# DAC_12bit.net
KiCad netlist of a schematic drawn in Altium Designer
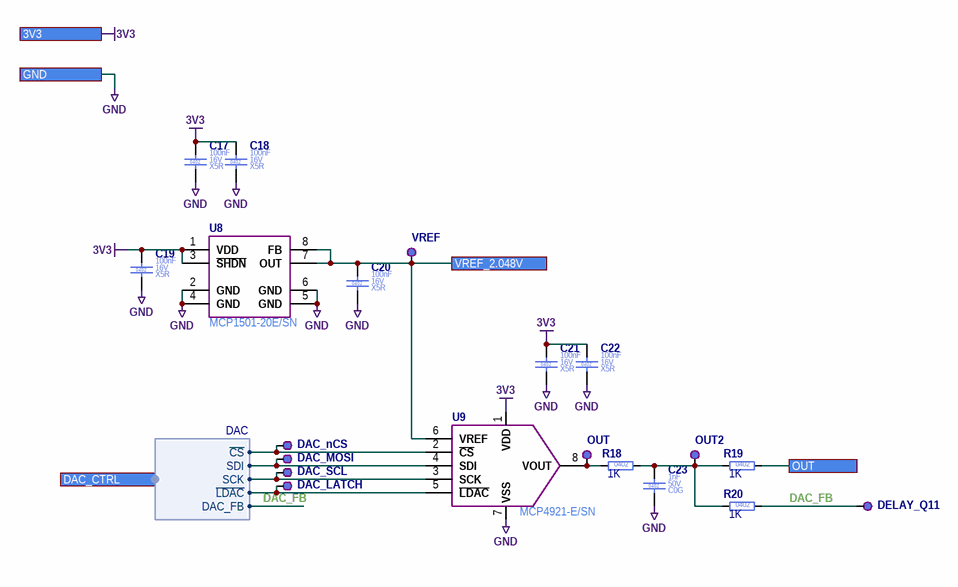
[diagram p0: DAC_12bit.SchDoc]

(export (version "E")
  (design (tool "Eeschema 10.0.6"))
  (components
    (comp (ref "C17")
      (value "C_100NF_16V_X5R_0402_10")
      (footprint "C_0402_1005")
      (description "Ceramic Capacitor")
      (fields
        (field (name "CASE/PACKAGE") "0402")
        (field (name "VOLTAGE RATING (DC)") "16V")
        (field (name "DIELECTRIC") "X5R")
        (field (name "CAPACITANCE") "100nF")
        (field (name "TOLERANCE") "10%")
        (field (name "MANUFACTURER PART NUMBER") "EMK105BJ104KV-F")
      )
      (libsource (lib "7Sigma") (part "C"))
    )
    (comp (ref "C18")
      (value "C_100NF_16V_X5R_0402_10")
      (footprint "C_0402_1005")
      (description "Ceramic Capacitor")
      (fields
        (field (name "CASE/PACKAGE") "0402")
        (field (name "VOLTAGE RATING (DC)") "16V")
        (field (name "DIELECTRIC") "X5R")
        (field (name "CAPACITANCE") "100nF")
        (field (name "TOLERANCE") "10%")
        (field (name "MANUFACTURER PART NUMBER") "EMK105BJ104KV-F")
      )
      (libsource (lib "7Sigma") (part "C"))
    )
    (comp (ref "C19")
      (value "C_100NF_16V_X5R_0402_10")
      (footprint "C_0402_1005")
      (description "Ceramic Capacitor")
      (fields
        (field (name "CASE/PACKAGE") "0402")
        (field (name "VOLTAGE RATING (DC)") "16V")
        (field (name "DIELECTRIC") "X5R")
        (field (name "CAPACITANCE") "100nF")
        (field (name "TOLERANCE") "10%")
        (field (name "MANUFACTURER PART NUMBER") "EMK105BJ104KV-F")
      )
      (libsource (lib "7Sigma") (part "C"))
    )
    (comp (ref "C20")
      (value "C_100NF_16V_X5R_0402_10")
      (footprint "C_0402_1005")
      (description "Ceramic Capacitor")
      (fields
        (field (name "CASE/PACKAGE") "0402")
        (field (name "VOLTAGE RATING (DC)") "16V")
        (field (name "DIELECTRIC") "X5R")
        (field (name "CAPACITANCE") "100nF")
        (field (name "TOLERANCE") "10%")
        (field (name "MANUFACTURER PART NUMBER") "EMK105BJ104KV-F")
      )
      (libsource (lib "7Sigma") (part "C"))
    )
    (comp (ref "C21")
      (value "C_100NF_16V_X5R_0402_10")
      (footprint "C_0402_1005")
      (description "Ceramic Capacitor")
      (fields
        (field (name "CASE/PACKAGE") "0402")
        (field (name "VOLTAGE RATING (DC)") "16V")
        (field (name "DIELECTRIC") "X5R")
        (field (name "CAPACITANCE") "100nF")
        (field (name "TOLERANCE") "10%")
        (field (name "MANUFACTURER PART NUMBER") "EMK105BJ104KV-F")
      )
      (libsource (lib "7Sigma") (part "C"))
    )
    (comp (ref "C22")
      (value "C_100NF_16V_X5R_0402_10")
      (footprint "C_0402_1005")
      (description "Ceramic Capacitor")
      (fields
        (field (name "CASE/PACKAGE") "0402")
        (field (name "VOLTAGE RATING (DC)") "16V")
        (field (name "DIELECTRIC") "X5R")
        (field (name "CAPACITANCE") "100nF")
        (field (name "TOLERANCE") "10%")
        (field (name "MANUFACTURER PART NUMBER") "EMK105BJ104KV-F")
      )
      (libsource (lib "7Sigma") (part "C"))
    )
    (comp (ref "C23")
      (value "C_1NF_50V_C0G_0402_5")
      (footprint "C_0402_1005")
      (description "Ceramic Capacitor")
      (fields
        (field (name "CASE/PACKAGE") "0402")
        (field (name "VOLTAGE RATING (DC)") "50V")
        (field (name "DIELECTRIC") "C0G")
        (field (name "CAPACITANCE") "1nF")
        (field (name "TOLERANCE") "5%")
        (field (name "MANUFACTURER PART NUMBER") "UMK105CG102JV-F")
      )
      (libsource (lib "7Sigma") (part "C"))
    )
    (comp (ref "DAC_LATCH")
      (value "TP_PAD_1.3MM")
      (footprint "TP_PAD_1.3MM")
      (description "Testpoint SMD 1.3mm")
      (libsource (lib "7Sigma") (part "TESTPOINT"))
    )
    (comp (ref "DAC_MOSI")
      (value "TP_PAD_1.3MM")
      (footprint "TP_PAD_1.3MM")
      (description "Testpoint SMD 1.3mm")
      (libsource (lib "7Sigma") (part "TESTPOINT"))
    )
    (comp (ref "DAC_nCS")
      (value "TP_PAD_1.3MM")
      (footprint "TP_PAD_1.3MM")
      (description "Testpoint SMD 1.3mm")
      (libsource (lib "7Sigma") (part "TESTPOINT"))
    )
    (comp (ref "DAC_SCL")
      (value "TP_PAD_1.3MM")
      (footprint "TP_PAD_1.3MM")
      (description "Testpoint SMD 1.3mm")
      (libsource (lib "7Sigma") (part "TESTPOINT"))
    )
    (comp (ref "DELAY_Q11")
      (value "TP_PAD_1.3MM")
      (footprint "TP_PAD_1.3MM")
      (description "Testpoint SMD 1.3mm")
      (libsource (lib "7Sigma") (part "TESTPOINT"))
    )
    (comp (ref "OUT")
      (value "TP_PAD_1.3MM")
      (footprint "TP_PAD_1.3MM")
      (description "Testpoint SMD 1.3mm")
      (libsource (lib "7Sigma") (part "TESTPOINT"))
    )
    (comp (ref "OUT2")
      (value "TP_PAD_1.3MM")
      (footprint "TP_PAD_1.3MM")
      (description "Testpoint SMD 1.3mm")
      (libsource (lib "7Sigma") (part "TESTPOINT"))
    )
    (comp (ref "R18")
      (value "R_1K_0402_1")
      (footprint "R_0402_1005")
      (description "Thick Film Resistor")
      (fields
        (field (name "RESISTANCE") "1K")
        (field (name "CASE/PACKAGE") "0402")
        (field (name "TOLERANCE") "1%")
        (field (name "MANUFACTURER") "Yageo")
      )
      (libsource (lib "7Sigma") (part "R"))
    )
    (comp (ref "R19")
      (value "R_1K_0402_1")
      (footprint "R_0402_1005")
      (description "Thick Film Resistor")
      (fields
        (field (name "RESISTANCE") "1K")
        (field (name "CASE/PACKAGE") "0402")
        (field (name "TOLERANCE") "1%")
        (field (name "MANUFACTURER") "Yageo")
      )
      (libsource (lib "7Sigma") (part "R"))
    )
    (comp (ref "R20")
      (value "R_1K_0402_1")
      (footprint "R_0402_1005")
      (description "Thick Film Resistor")
      (fields
        (field (name "RESISTANCE") "1K")
        (field (name "CASE/PACKAGE") "0402")
        (field (name "TOLERANCE") "1%")
        (field (name "MANUFACTURER") "Yageo")
      )
      (libsource (lib "7Sigma") (part "R"))
    )
    (comp (ref "U8")
      (value "MCP1501_SOIC")
      (footprint "SOIC127P600X170-8N")
      (description "2.048V Voltage References Precision Buffered Voltage Reference")
      (fields
        (field (name "PART NUMBER") "MCP1501-20E/SN")
        (field (name "MANUFACTURER PART NUMBER") "MCP1501-20E/SN")
        (field (name "MANUFACTURER") "Microchip Technology")
      )
      (libsource (lib "7Sigma") (part "MCP1501_SOIC"))
    )
    (comp (ref "U9")
      (value "MCP4921-E/SN")
      (footprint "SOIC127P600X170-8N")
      (description "1 Channel DAC 12 bit")
      (fields
        (field (name "MANUFACTURER PART NUMBER") "MCP4921-E/SN")
        (field (name "MANUFACTURER") "Microchip")
      )
      (libsource (lib "7Sigma") (part "MCP4921"))
    )
    (comp (ref "VREF")
      (value "TP_PAD_1.3MM")
      (footprint "TP_PAD_1.3MM")
      (description "Testpoint SMD 1.3mm")
      (libsource (lib "7Sigma") (part "TESTPOINT"))
    )
  )
  (nets
    (net (code "2") (name "/DAC_FB") (class "Default")
      (node (ref "DELAY_Q11") (pin "1") (pinfunction "TP_1") (pintype "passive"))
      (node (ref "R20") (pin "2") (pinfunction "2_2") (pintype "passive"))
    )
    (net (code "3") (name "/OUT") (class "Default")
      (node (ref "R19") (pin "2") (pinfunction "2_2") (pintype "passive"))
    )
    (net (code "4") (name "/VREF_2.048V") (class "Default")
      (node (ref "C20") (pin "1") (pinfunction "1_1") (pintype "passive"))
      (node (ref "U8") (pin "7") (pinfunction "OUT_7") (pintype "passive"))
      (node (ref "U8") (pin "8") (pinfunction "FB_8") (pintype "passive"))
      (node (ref "U9") (pin "6") (pinfunction "VREF_6") (pintype "passive"))
      (node (ref "VREF") (pin "1") (pinfunction "TP_1") (pintype "passive"))
    )
    (net (code "6") (name "3V3") (class "Default")
      (node (ref "C17") (pin "1") (pinfunction "1_1") (pintype "passive"))
      (node (ref "C18") (pin "1") (pinfunction "1_1") (pintype "passive"))
      (node (ref "C19") (pin "1") (pinfunction "1_1") (pintype "passive"))
      (node (ref "C21") (pin "1") (pinfunction "1_1") (pintype "passive"))
      (node (ref "C22") (pin "1") (pinfunction "1_1") (pintype "passive"))
      (node (ref "U8") (pin "1") (pinfunction "VDD_1") (pintype "passive"))
      (node (ref "U8") (pin "3") (pinfunction "SHDN_3") (pintype "passive"))
      (node (ref "U9") (pin "1") (pinfunction "VDD_1") (pintype "passive"))
    )
    (net (code "7") (name "GND") (class "Default")
      (node (ref "C17") (pin "2") (pinfunction "2_2") (pintype "passive"))
      (node (ref "C18") (pin "2") (pinfunction "2_2") (pintype "passive"))
      (node (ref "C19") (pin "2") (pinfunction "2_2") (pintype "passive"))
      (node (ref "C20") (pin "2") (pinfunction "2_2") (pintype "passive"))
      (node (ref "C21") (pin "2") (pinfunction "2_2") (pintype "passive"))
      (node (ref "C22") (pin "2") (pinfunction "2_2") (pintype "passive"))
      (node (ref "C23") (pin "2") (pinfunction "2_2") (pintype "passive"))
      (node (ref "U8") (pin "2") (pinfunction "GND_2") (pintype "passive"))
      (node (ref "U8") (pin "4") (pinfunction "GND_4") (pintype "passive"))
      (node (ref "U8") (pin "5") (pinfunction "GND_5") (pintype "passive"))
      (node (ref "U8") (pin "6") (pinfunction "GND_6") (pintype "passive"))
      (node (ref "U9") (pin "7") (pinfunction "VSS_7") (pintype "passive"))
    )
    (net (code "8") (name "Net-(DAC_LATCH-TP)") (class "Default")
      (node (ref "DAC_LATCH") (pin "1") (pinfunction "TP_1") (pintype "passive"))
      (node (ref "U9") (pin "5") (pinfunction "LDAC_5") (pintype "passive"))
    )
    (net (code "9") (name "Net-(DAC_MOSI-TP)") (class "Default")
      (node (ref "DAC_MOSI") (pin "1") (pinfunction "TP_1") (pintype "passive"))
      (node (ref "U9") (pin "4") (pinfunction "SDI_4") (pintype "passive"))
    )
    (net (code "10") (name "Net-(DAC_SCL-TP)") (class "Default")
      (node (ref "DAC_SCL") (pin "1") (pinfunction "TP_1") (pintype "passive"))
      (node (ref "U9") (pin "3") (pinfunction "SCK_3") (pintype "passive"))
    )
    (net (code "11") (name "Net-(DAC_nCS-TP)") (class "Default")
      (node (ref "DAC_nCS") (pin "1") (pinfunction "TP_1") (pintype "passive"))
      (node (ref "U9") (pin "2") (pinfunction "CS_2") (pintype "passive"))
    )
    (net (code "12") (name "Net-(OUT-TP)") (class "Default")
      (node (ref "OUT") (pin "1") (pinfunction "TP_1") (pintype "passive"))
      (node (ref "R18") (pin "1") (pinfunction "1_1") (pintype "passive"))
      (node (ref "U9") (pin "8") (pinfunction "VOUT_8") (pintype "passive"))
    )
    (net (code "13") (name "Net-(OUT2-TP)") (class "Default")
      (node (ref "C23") (pin "1") (pinfunction "1_1") (pintype "passive"))
      (node (ref "OUT2") (pin "1") (pinfunction "TP_1") (pintype "passive"))
      (node (ref "R18") (pin "2") (pinfunction "2_2") (pintype "passive"))
      (node (ref "R19") (pin "1") (pinfunction "1_1") (pintype "passive"))
      (node (ref "R20") (pin "1") (pinfunction "1_1") (pintype "passive"))
    )
  )
)
